# PenAndPaper.net
KiCad netlist of a schematic drawn in Altium Designer
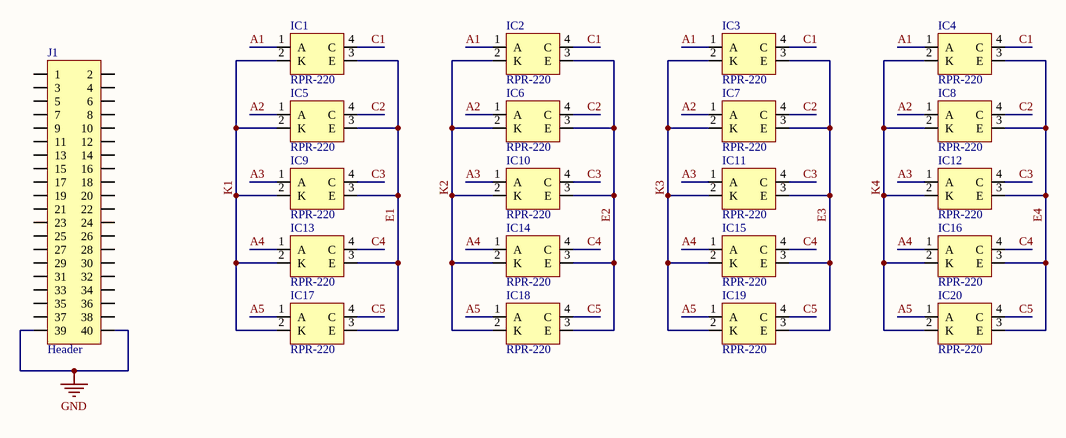
[diagram p0: PenAndPaper.SchDoc]

(export (version "E")
  (design (tool "Eeschema 10.0.6"))
  (components
    (comp (ref "IC1")
      (value "RPR-220")
      (footprint "RPR_220")
      (description "Infrared Reflex Photosensor")
      (libsource (lib "Components") (part "RPR-220"))
    )
    (comp (ref "IC2")
      (value "RPR-220")
      (footprint "RPR_220")
      (description "Infrared Reflex Photosensor")
      (libsource (lib "Components") (part "RPR-220"))
    )
    (comp (ref "IC3")
      (value "RPR-220")
      (footprint "RPR_220")
      (description "Infrared Reflex Photosensor")
      (libsource (lib "Components") (part "RPR-220"))
    )
    (comp (ref "IC4")
      (value "RPR-220")
      (footprint "RPR_220")
      (description "Infrared Reflex Photosensor")
      (libsource (lib "Components") (part "RPR-220"))
    )
    (comp (ref "IC5")
      (value "RPR-220")
      (footprint "RPR_220")
      (description "Infrared Reflex Photosensor")
      (libsource (lib "Components") (part "RPR-220"))
    )
    (comp (ref "IC6")
      (value "RPR-220")
      (footprint "RPR_220")
      (description "Infrared Reflex Photosensor")
      (libsource (lib "Components") (part "RPR-220"))
    )
    (comp (ref "IC7")
      (value "RPR-220")
      (footprint "RPR_220")
      (description "Infrared Reflex Photosensor")
      (libsource (lib "Components") (part "RPR-220"))
    )
    (comp (ref "IC8")
      (value "RPR-220")
      (footprint "RPR_220")
      (description "Infrared Reflex Photosensor")
      (libsource (lib "Components") (part "RPR-220"))
    )
    (comp (ref "IC9")
      (value "RPR-220")
      (footprint "RPR_220")
      (description "Infrared Reflex Photosensor")
      (libsource (lib "Components") (part "RPR-220"))
    )
    (comp (ref "IC10")
      (value "RPR-220")
      (footprint "RPR_220")
      (description "Infrared Reflex Photosensor")
      (libsource (lib "Components") (part "RPR-220"))
    )
    (comp (ref "IC11")
      (value "RPR-220")
      (footprint "RPR_220")
      (description "Infrared Reflex Photosensor")
      (libsource (lib "Components") (part "RPR-220"))
    )
    (comp (ref "IC12")
      (value "RPR-220")
      (footprint "RPR_220")
      (description "Infrared Reflex Photosensor")
      (libsource (lib "Components") (part "RPR-220"))
    )
    (comp (ref "IC13")
      (value "RPR-220")
      (footprint "RPR_220")
      (description "Infrared Reflex Photosensor")
      (libsource (lib "Components") (part "RPR-220"))
    )
    (comp (ref "IC14")
      (value "RPR-220")
      (footprint "RPR_220")
      (description "Infrared Reflex Photosensor")
      (libsource (lib "Components") (part "RPR-220"))
    )
    (comp (ref "IC15")
      (value "RPR-220")
      (footprint "RPR_220")
      (description "Infrared Reflex Photosensor")
      (libsource (lib "Components") (part "RPR-220"))
    )
    (comp (ref "IC16")
      (value "RPR-220")
      (footprint "RPR_220")
      (description "Infrared Reflex Photosensor")
      (libsource (lib "Components") (part "RPR-220"))
    )
    (comp (ref "IC17")
      (value "RPR-220")
      (footprint "RPR_220")
      (description "Infrared Reflex Photosensor")
      (libsource (lib "Components") (part "RPR-220"))
    )
    (comp (ref "IC18")
      (value "RPR-220")
      (footprint "RPR_220")
      (description "Infrared Reflex Photosensor")
      (libsource (lib "Components") (part "RPR-220"))
    )
    (comp (ref "IC19")
      (value "RPR-220")
      (footprint "RPR_220")
      (description "Infrared Reflex Photosensor")
      (libsource (lib "Components") (part "RPR-220"))
    )
    (comp (ref "IC20")
      (value "RPR-220")
      (footprint "RPR_220")
      (description "Infrared Reflex Photosensor")
      (libsource (lib "Components") (part "RPR-220"))
    )
    (comp (ref "J1")
      (value "Header")
      (footprint "PINHD_2.54_2X40")
      (description "Pin Header 2x40P")
      (libsource (lib "Components") (part "PINHD_2x40"))
    )
  )
  (nets
    (net (code "1") (name "/A1") (class "Default")
      (node (ref "IC1") (pin "1") (pinfunction "A_1") (pintype "passive"))
      (node (ref "IC2") (pin "1") (pinfunction "A_1") (pintype "passive"))
      (node (ref "IC3") (pin "1") (pinfunction "A_1") (pintype "passive"))
      (node (ref "IC4") (pin "1") (pinfunction "A_1") (pintype "passive"))
    )
    (net (code "2") (name "/A2") (class "Default")
      (node (ref "IC5") (pin "1") (pinfunction "A_1") (pintype "passive"))
      (node (ref "IC6") (pin "1") (pinfunction "A_1") (pintype "passive"))
      (node (ref "IC7") (pin "1") (pinfunction "A_1") (pintype "passive"))
      (node (ref "IC8") (pin "1") (pinfunction "A_1") (pintype "passive"))
    )
    (net (code "3") (name "/A3") (class "Default")
      (node (ref "IC10") (pin "1") (pinfunction "A_1") (pintype "passive"))
      (node (ref "IC11") (pin "1") (pinfunction "A_1") (pintype "passive"))
      (node (ref "IC12") (pin "1") (pinfunction "A_1") (pintype "passive"))
      (node (ref "IC9") (pin "1") (pinfunction "A_1") (pintype "passive"))
    )
    (net (code "4") (name "/A4") (class "Default")
      (node (ref "IC13") (pin "1") (pinfunction "A_1") (pintype "passive"))
      (node (ref "IC14") (pin "1") (pinfunction "A_1") (pintype "passive"))
      (node (ref "IC15") (pin "1") (pinfunction "A_1") (pintype "passive"))
      (node (ref "IC16") (pin "1") (pinfunction "A_1") (pintype "passive"))
    )
    (net (code "5") (name "/A5") (class "Default")
      (node (ref "IC17") (pin "1") (pinfunction "A_1") (pintype "passive"))
      (node (ref "IC18") (pin "1") (pinfunction "A_1") (pintype "passive"))
      (node (ref "IC19") (pin "1") (pinfunction "A_1") (pintype "passive"))
      (node (ref "IC20") (pin "1") (pinfunction "A_1") (pintype "passive"))
    )
    (net (code "6") (name "/C1") (class "Default")
      (node (ref "IC1") (pin "4") (pinfunction "C_4") (pintype "passive"))
      (node (ref "IC2") (pin "4") (pinfunction "C_4") (pintype "passive"))
      (node (ref "IC3") (pin "4") (pinfunction "C_4") (pintype "passive"))
      (node (ref "IC4") (pin "4") (pinfunction "C_4") (pintype "passive"))
    )
    (net (code "7") (name "/C2") (class "Default")
      (node (ref "IC5") (pin "4") (pinfunction "C_4") (pintype "passive"))
      (node (ref "IC6") (pin "4") (pinfunction "C_4") (pintype "passive"))
      (node (ref "IC7") (pin "4") (pinfunction "C_4") (pintype "passive"))
      (node (ref "IC8") (pin "4") (pinfunction "C_4") (pintype "passive"))
    )
    (net (code "8") (name "/C3") (class "Default")
      (node (ref "IC10") (pin "4") (pinfunction "C_4") (pintype "passive"))
      (node (ref "IC11") (pin "4") (pinfunction "C_4") (pintype "passive"))
      (node (ref "IC12") (pin "4") (pinfunction "C_4") (pintype "passive"))
      (node (ref "IC9") (pin "4") (pinfunction "C_4") (pintype "passive"))
    )
    (net (code "9") (name "/C4") (class "Default")
      (node (ref "IC13") (pin "4") (pinfunction "C_4") (pintype "passive"))
      (node (ref "IC14") (pin "4") (pinfunction "C_4") (pintype "passive"))
      (node (ref "IC15") (pin "4") (pinfunction "C_4") (pintype "passive"))
      (node (ref "IC16") (pin "4") (pinfunction "C_4") (pintype "passive"))
    )
    (net (code "10") (name "/C5") (class "Default")
      (node (ref "IC17") (pin "4") (pinfunction "C_4") (pintype "passive"))
      (node (ref "IC18") (pin "4") (pinfunction "C_4") (pintype "passive"))
      (node (ref "IC19") (pin "4") (pinfunction "C_4") (pintype "passive"))
      (node (ref "IC20") (pin "4") (pinfunction "C_4") (pintype "passive"))
    )
    (net (code "11") (name "/E1") (class "Default")
      (node (ref "IC1") (pin "3") (pinfunction "E_3") (pintype "passive"))
      (node (ref "IC13") (pin "3") (pinfunction "E_3") (pintype "passive"))
      (node (ref "IC17") (pin "3") (pinfunction "E_3") (pintype "passive"))
      (node (ref "IC5") (pin "3") (pinfunction "E_3") (pintype "passive"))
      (node (ref "IC9") (pin "3") (pinfunction "E_3") (pintype "passive"))
    )
    (net (code "12") (name "/E2") (class "Default")
      (node (ref "IC10") (pin "3") (pinfunction "E_3") (pintype "passive"))
      (node (ref "IC14") (pin "3") (pinfunction "E_3") (pintype "passive"))
      (node (ref "IC18") (pin "3") (pinfunction "E_3") (pintype "passive"))
      (node (ref "IC2") (pin "3") (pinfunction "E_3") (pintype "passive"))
      (node (ref "IC6") (pin "3") (pinfunction "E_3") (pintype "passive"))
    )
    (net (code "13") (name "/E3") (class "Default")
      (node (ref "IC11") (pin "3") (pinfunction "E_3") (pintype "passive"))
      (node (ref "IC15") (pin "3") (pinfunction "E_3") (pintype "passive"))
      (node (ref "IC19") (pin "3") (pinfunction "E_3") (pintype "passive"))
      (node (ref "IC3") (pin "3") (pinfunction "E_3") (pintype "passive"))
      (node (ref "IC7") (pin "3") (pinfunction "E_3") (pintype "passive"))
    )
    (net (code "14") (name "/E4") (class "Default")
      (node (ref "IC12") (pin "3") (pinfunction "E_3") (pintype "passive"))
      (node (ref "IC16") (pin "3") (pinfunction "E_3") (pintype "passive"))
      (node (ref "IC20") (pin "3") (pinfunction "E_3") (pintype "passive"))
      (node (ref "IC4") (pin "3") (pinfunction "E_3") (pintype "passive"))
      (node (ref "IC8") (pin "3") (pinfunction "E_3") (pintype "passive"))
    )
    (net (code "15") (name "/K1") (class "Default")
      (node (ref "IC1") (pin "2") (pinfunction "K_2") (pintype "passive"))
      (node (ref "IC13") (pin "2") (pinfunction "K_2") (pintype "passive"))
      (node (ref "IC17") (pin "2") (pinfunction "K_2") (pintype "passive"))
      (node (ref "IC5") (pin "2") (pinfunction "K_2") (pintype "passive"))
      (node (ref "IC9") (pin "2") (pinfunction "K_2") (pintype "passive"))
    )
    (net (code "16") (name "/K2") (class "Default")
      (node (ref "IC10") (pin "2") (pinfunction "K_2") (pintype "passive"))
      (node (ref "IC14") (pin "2") (pinfunction "K_2") (pintype "passive"))
      (node (ref "IC18") (pin "2") (pinfunction "K_2") (pintype "passive"))
      (node (ref "IC2") (pin "2") (pinfunction "K_2") (pintype "passive"))
      (node (ref "IC6") (pin "2") (pinfunction "K_2") (pintype "passive"))
    )
    (net (code "17") (name "/K3") (class "Default")
      (node (ref "IC11") (pin "2") (pinfunction "K_2") (pintype "passive"))
      (node (ref "IC15") (pin "2") (pinfunction "K_2") (pintype "passive"))
      (node (ref "IC19") (pin "2") (pinfunction "K_2") (pintype "passive"))
      (node (ref "IC3") (pin "2") (pinfunction "K_2") (pintype "passive"))
      (node (ref "IC7") (pin "2") (pinfunction "K_2") (pintype "passive"))
    )
    (net (code "18") (name "/K4") (class "Default")
      (node (ref "IC12") (pin "2") (pinfunction "K_2") (pintype "passive"))
      (node (ref "IC16") (pin "2") (pinfunction "K_2") (pintype "passive"))
      (node (ref "IC20") (pin "2") (pinfunction "K_2") (pintype "passive"))
      (node (ref "IC4") (pin "2") (pinfunction "K_2") (pintype "passive"))
      (node (ref "IC8") (pin "2") (pinfunction "K_2") (pintype "passive"))
    )
    (net (code "19") (name "GND") (class "Default")
      (node (ref "J1") (pin "39") (pinfunction "39_39") (pintype "passive"))
      (node (ref "J1") (pin "40") (pinfunction "40_40") (pintype "passive"))
    )
    (net (code "20") (name "unconnected-(J1-Pad1)") (class "Default")
      (node (ref "J1") (pin "1") (pinfunction "1_1") (pintype "passive"))
    )
    (net (code "21") (name "unconnected-(J1-Pad2)") (class "Default")
      (node (ref "J1") (pin "2") (pinfunction "2_2") (pintype "passive"))
    )
    (net (code "22") (name "unconnected-(J1-Pad3)") (class "Default")
      (node (ref "J1") (pin "3") (pinfunction "3_3") (pintype "passive"))
    )
    (net (code "23") (name "unconnected-(J1-Pad4)") (class "Default")
      (node (ref "J1") (pin "4") (pinfunction "4_4") (pintype "passive"))
    )
    (net (code "24") (name "unconnected-(J1-Pad5)") (class "Default")
      (node (ref "J1") (pin "5") (pinfunction "5_5") (pintype "passive"))
    )
    (net (code "25") (name "unconnected-(J1-Pad6)") (class "Default")
      (node (ref "J1") (pin "6") (pinfunction "6_6") (pintype "passive"))
    )
    (net (code "26") (name "unconnected-(J1-Pad7)") (class "Default")
      (node (ref "J1") (pin "7") (pinfunction "7_7") (pintype "passive"))
    )
    (net (code "27") (name "unconnected-(J1-Pad8)") (class "Default")
      (node (ref "J1") (pin "8") (pinfunction "8_8") (pintype "passive"))
    )
    (net (code "28") (name "unconnected-(J1-Pad9)") (class "Default")
      (node (ref "J1") (pin "9") (pinfunction "9_9") (pintype "passive"))
    )
    (net (code "29") (name "unconnected-(J1-Pad10)") (class "Default")
      (node (ref "J1") (pin "10") (pinfunction "10_10") (pintype "passive"))
    )
    (net (code "30") (name "unconnected-(J1-Pad11)") (class "Default")
      (node (ref "J1") (pin "11") (pinfunction "11_11") (pintype "passive"))
    )
    (net (code "31") (name "unconnected-(J1-Pad12)") (class "Default")
      (node (ref "J1") (pin "12") (pinfunction "12_12") (pintype "passive"))
    )
    (net (code "32") (name "unconnected-(J1-Pad13)") (class "Default")
      (node (ref "J1") (pin "13") (pinfunction "13_13") (pintype "passive"))
    )
    (net (code "33") (name "unconnected-(J1-Pad14)") (class "Default")
      (node (ref "J1") (pin "14") (pinfunction "14_14") (pintype "passive"))
    )
    (net (code "34") (name "unconnected-(J1-Pad15)") (class "Default")
      (node (ref "J1") (pin "15") (pinfunction "15_15") (pintype "passive"))
    )
    (net (code "35") (name "unconnected-(J1-Pad16)") (class "Default")
      (node (ref "J1") (pin "16") (pinfunction "16_16") (pintype "passive"))
    )
    (net (code "36") (name "unconnected-(J1-Pad17)") (class "Default")
      (node (ref "J1") (pin "17") (pinfunction "17_17") (pintype "passive"))
    )
    (net (code "37") (name "unconnected-(J1-Pad18)") (class "Default")
      (node (ref "J1") (pin "18") (pinfunction "18_18") (pintype "passive"))
    )
    (net (code "38") (name "unconnected-(J1-Pad19)") (class "Default")
      (node (ref "J1") (pin "19") (pinfunction "19_19") (pintype "passive"))
    )
    (net (code "39") (name "unconnected-(J1-Pad20)") (class "Default")
      (node (ref "J1") (pin "20") (pinfunction "20_20") (pintype "passive"))
    )
    (net (code "40") (name "unconnected-(J1-Pad21)") (class "Default")
      (node (ref "J1") (pin "21") (pinfunction "21_21") (pintype "passive"))
    )
    (net (code "41") (name "unconnected-(J1-Pad22)") (class "Default")
      (node (ref "J1") (pin "22") (pinfunction "22_22") (pintype "passive"))
    )
    (net (code "42") (name "unconnected-(J1-Pad23)") (class "Default")
      (node (ref "J1") (pin "23") (pinfunction "23_23") (pintype "passive"))
    )
    (net (code "43") (name "unconnected-(J1-Pad24)") (class "Default")
      (node (ref "J1") (pin "24") (pinfunction "24_24") (pintype "passive"))
    )
    (net (code "44") (name "unconnected-(J1-Pad25)") (class "Default")
      (node (ref "J1") (pin "25") (pinfunction "25_25") (pintype "passive"))
    )
    (net (code "45") (name "unconnected-(J1-Pad26)") (class "Default")
      (node (ref "J1") (pin "26") (pinfunction "26_26") (pintype "passive"))
    )
    (net (code "46") (name "unconnected-(J1-Pad27)") (class "Default")
      (node (ref "J1") (pin "27") (pinfunction "27_27") (pintype "passive"))
    )
    (net (code "47") (name "unconnected-(J1-Pad28)") (class "Default")
      (node (ref "J1") (pin "28") (pinfunction "28_28") (pintype "passive"))
    )
    (net (code "48") (name "unconnected-(J1-Pad29)") (class "Default")
      (node (ref "J1") (pin "29") (pinfunction "29_29") (pintype "passive"))
    )
    (net (code "49") (name "unconnected-(J1-Pad30)") (class "Default")
      (node (ref "J1") (pin "30") (pinfunction "30_30") (pintype "passive"))
    )
    (net (code "50") (name "unconnected-(J1-Pad31)") (class "Default")
      (node (ref "J1") (pin "31") (pinfunction "31_31") (pintype "passive"))
    )
    (net (code "51") (name "unconnected-(J1-Pad32)") (class "Default")
      (node (ref "J1") (pin "32") (pinfunction "32_32") (pintype "passive"))
    )
    (net (code "52") (name "unconnected-(J1-Pad33)") (class "Default")
      (node (ref "J1") (pin "33") (pinfunction "33_33") (pintype "passive"))
    )
    (net (code "53") (name "unconnected-(J1-Pad34)") (class "Default")
      (node (ref "J1") (pin "34") (pinfunction "34_34") (pintype "passive"))
    )
    (net (code "54") (name "unconnected-(J1-Pad35)") (class "Default")
      (node (ref "J1") (pin "35") (pinfunction "35_35") (pintype "passive"))
    )
    (net (code "55") (name "unconnected-(J1-Pad36)") (class "Default")
      (node (ref "J1") (pin "36") (pinfunction "36_36") (pintype "passive"))
    )
    (net (code "56") (name "unconnected-(J1-Pad37)") (class "Default")
      (node (ref "J1") (pin "37") (pinfunction "37_37") (pintype "passive"))
    )
    (net (code "57") (name "unconnected-(J1-Pad38)") (class "Default")
      (node (ref "J1") (pin "38") (pinfunction "38_38") (pintype "passive"))
    )
  )
)
